# apa102-2020-stick.net
KiCad netlist of a schematic drawn in EAGLE
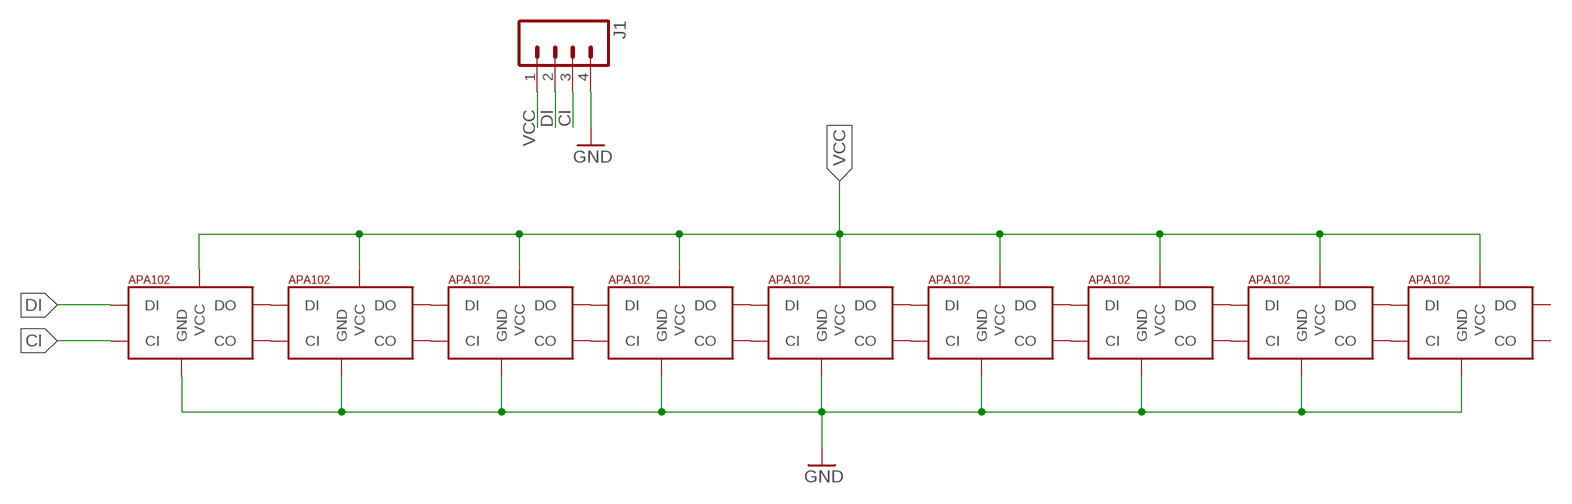
[diagram p0: schematic, sheet 1]

(export (version "E")
  (design (tool "Eeschema 10.0.6"))
  (components
    (comp (ref "J1")
      (value "M04LOCK")
      (footprint "eagle-import:1X04_LOCK")
      (libsource (lib "eagle-import") (part "M04LOCK"))
    )
    (comp (ref "U$1")
      (value "APA1022020")
      (footprint "eagle-import:APA102_2020")
      (libsource (lib "eagle-import") (part "APA1022020"))
    )
    (comp (ref "U$2")
      (value "APA1022020")
      (footprint "eagle-import:APA102_2020")
      (libsource (lib "eagle-import") (part "APA1022020"))
    )
    (comp (ref "U$3")
      (value "APA1022020")
      (footprint "eagle-import:APA102_2020")
      (libsource (lib "eagle-import") (part "APA1022020"))
    )
    (comp (ref "U$4")
      (value "APA1022020")
      (footprint "eagle-import:APA102_2020")
      (libsource (lib "eagle-import") (part "APA1022020"))
    )
    (comp (ref "U$5")
      (value "APA1022020")
      (footprint "eagle-import:APA102_2020")
      (libsource (lib "eagle-import") (part "APA1022020"))
    )
    (comp (ref "U$6")
      (value "APA1022020")
      (footprint "eagle-import:APA102_2020")
      (libsource (lib "eagle-import") (part "APA1022020"))
    )
    (comp (ref "U$7")
      (value "APA1022020")
      (footprint "eagle-import:APA102_2020")
      (libsource (lib "eagle-import") (part "APA1022020"))
    )
    (comp (ref "U$8")
      (value "APA1022020")
      (footprint "eagle-import:APA102_2020")
      (libsource (lib "eagle-import") (part "APA1022020"))
    )
    (comp (ref "U$9")
      (value "APA1022020")
      (footprint "eagle-import:APA102_2020")
      (libsource (lib "eagle-import") (part "APA1022020"))
    )
  )
  (nets
    (net (code "1") (name "CI") (class "Default")
      (node (ref "J1") (pin "3") (pinfunction "3_3") (pintype "passive"))
      (node (ref "U$1") (pin "C_IN") (pinfunction "CI_C_IN") (pintype "bidirectional"))
    )
    (net (code "2") (name "DI") (class "Default")
      (node (ref "J1") (pin "2") (pinfunction "2_2") (pintype "passive"))
      (node (ref "U$1") (pin "D_IN") (pinfunction "DI_D_IN") (pintype "bidirectional"))
    )
    (net (code "3") (name "GND") (class "Default")
      (node (ref "J1") (pin "4") (pinfunction "4_4") (pintype "passive"))
      (node (ref "U$1") (pin "GND") (pinfunction "GND_GND") (pintype "bidirectional"))
      (node (ref "U$2") (pin "GND") (pinfunction "GND_GND") (pintype "bidirectional"))
      (node (ref "U$3") (pin "GND") (pinfunction "GND_GND") (pintype "bidirectional"))
      (node (ref "U$4") (pin "GND") (pinfunction "GND_GND") (pintype "bidirectional"))
      (node (ref "U$5") (pin "GND") (pinfunction "GND_GND") (pintype "bidirectional"))
      (node (ref "U$6") (pin "GND") (pinfunction "GND_GND") (pintype "bidirectional"))
      (node (ref "U$7") (pin "GND") (pinfunction "GND_GND") (pintype "bidirectional"))
      (node (ref "U$8") (pin "GND") (pinfunction "GND_GND") (pintype "bidirectional"))
      (node (ref "U$9") (pin "GND") (pinfunction "GND_GND") (pintype "bidirectional"))
    )
    (net (code "4") (name "Net-(U$1-CO)") (class "Default")
      (node (ref "U$1") (pin "CL_OUT") (pinfunction "CO_CL_OUT") (pintype "bidirectional"))
      (node (ref "U$2") (pin "C_IN") (pinfunction "CI_C_IN") (pintype "bidirectional"))
    )
    (net (code "5") (name "Net-(U$1-DO)") (class "Default")
      (node (ref "U$1") (pin "D_OUT") (pinfunction "DO_D_OUT") (pintype "bidirectional"))
      (node (ref "U$2") (pin "D_IN") (pinfunction "DI_D_IN") (pintype "bidirectional"))
    )
    (net (code "6") (name "Net-(U$2-CO)") (class "Default")
      (node (ref "U$2") (pin "CL_OUT") (pinfunction "CO_CL_OUT") (pintype "bidirectional"))
      (node (ref "U$3") (pin "C_IN") (pinfunction "CI_C_IN") (pintype "bidirectional"))
    )
    (net (code "7") (name "Net-(U$2-DO)") (class "Default")
      (node (ref "U$2") (pin "D_OUT") (pinfunction "DO_D_OUT") (pintype "bidirectional"))
      (node (ref "U$3") (pin "D_IN") (pinfunction "DI_D_IN") (pintype "bidirectional"))
    )
    (net (code "8") (name "Net-(U$3-CO)") (class "Default")
      (node (ref "U$3") (pin "CL_OUT") (pinfunction "CO_CL_OUT") (pintype "bidirectional"))
      (node (ref "U$4") (pin "C_IN") (pinfunction "CI_C_IN") (pintype "bidirectional"))
    )
    (net (code "9") (name "Net-(U$3-DO)") (class "Default")
      (node (ref "U$3") (pin "D_OUT") (pinfunction "DO_D_OUT") (pintype "bidirectional"))
      (node (ref "U$4") (pin "D_IN") (pinfunction "DI_D_IN") (pintype "bidirectional"))
    )
    (net (code "10") (name "Net-(U$4-CO)") (class "Default")
      (node (ref "U$4") (pin "CL_OUT") (pinfunction "CO_CL_OUT") (pintype "bidirectional"))
      (node (ref "U$5") (pin "C_IN") (pinfunction "CI_C_IN") (pintype "bidirectional"))
    )
    (net (code "11") (name "Net-(U$4-DO)") (class "Default")
      (node (ref "U$4") (pin "D_OUT") (pinfunction "DO_D_OUT") (pintype "bidirectional"))
      (node (ref "U$5") (pin "D_IN") (pinfunction "DI_D_IN") (pintype "bidirectional"))
    )
    (net (code "12") (name "Net-(U$5-CO)") (class "Default")
      (node (ref "U$5") (pin "CL_OUT") (pinfunction "CO_CL_OUT") (pintype "bidirectional"))
      (node (ref "U$6") (pin "C_IN") (pinfunction "CI_C_IN") (pintype "bidirectional"))
    )
    (net (code "13") (name "Net-(U$5-DO)") (class "Default")
      (node (ref "U$5") (pin "D_OUT") (pinfunction "DO_D_OUT") (pintype "bidirectional"))
      (node (ref "U$6") (pin "D_IN") (pinfunction "DI_D_IN") (pintype "bidirectional"))
    )
    (net (code "14") (name "Net-(U$6-CO)") (class "Default")
      (node (ref "U$6") (pin "CL_OUT") (pinfunction "CO_CL_OUT") (pintype "bidirectional"))
      (node (ref "U$7") (pin "C_IN") (pinfunction "CI_C_IN") (pintype "bidirectional"))
    )
    (net (code "15") (name "Net-(U$6-DO)") (class "Default")
      (node (ref "U$6") (pin "D_OUT") (pinfunction "DO_D_OUT") (pintype "bidirectional"))
      (node (ref "U$7") (pin "D_IN") (pinfunction "DI_D_IN") (pintype "bidirectional"))
    )
    (net (code "16") (name "Net-(U$7-CO)") (class "Default")
      (node (ref "U$7") (pin "CL_OUT") (pinfunction "CO_CL_OUT") (pintype "bidirectional"))
      (node (ref "U$8") (pin "C_IN") (pinfunction "CI_C_IN") (pintype "bidirectional"))
    )
    (net (code "17") (name "Net-(U$7-DO)") (class "Default")
      (node (ref "U$7") (pin "D_OUT") (pinfunction "DO_D_OUT") (pintype "bidirectional"))
      (node (ref "U$8") (pin "D_IN") (pinfunction "DI_D_IN") (pintype "bidirectional"))
    )
    (net (code "18") (name "Net-(U$8-CO)") (class "Default")
      (node (ref "U$8") (pin "CL_OUT") (pinfunction "CO_CL_OUT") (pintype "bidirectional"))
      (node (ref "U$9") (pin "C_IN") (pinfunction "CI_C_IN") (pintype "bidirectional"))
    )
    (net (code "19") (name "Net-(U$8-DO)") (class "Default")
      (node (ref "U$8") (pin "D_OUT") (pinfunction "DO_D_OUT") (pintype "bidirectional"))
      (node (ref "U$9") (pin "D_IN") (pinfunction "DI_D_IN") (pintype "bidirectional"))
    )
    (net (code "20") (name "VCC") (class "Default")
      (node (ref "J1") (pin "1") (pinfunction "1_1") (pintype "passive"))
      (node (ref "U$1") (pin "V_CC") (pinfunction "VCC_V_CC") (pintype "bidirectional"))
      (node (ref "U$2") (pin "V_CC") (pinfunction "VCC_V_CC") (pintype "bidirectional"))
      (node (ref "U$3") (pin "V_CC") (pinfunction "VCC_V_CC") (pintype "bidirectional"))
      (node (ref "U$4") (pin "V_CC") (pinfunction "VCC_V_CC") (pintype "bidirectional"))
      (node (ref "U$5") (pin "V_CC") (pinfunction "VCC_V_CC") (pintype "bidirectional"))
      (node (ref "U$6") (pin "V_CC") (pinfunction "VCC_V_CC") (pintype "bidirectional"))
      (node (ref "U$7") (pin "V_CC") (pinfunction "VCC_V_CC") (pintype "bidirectional"))
      (node (ref "U$8") (pin "V_CC") (pinfunction "VCC_V_CC") (pintype "bidirectional"))
      (node (ref "U$9") (pin "V_CC") (pinfunction "VCC_V_CC") (pintype "bidirectional"))
    )
    (net (code "21") (name "unconnected-(U$9-CO-PadCL_OUT)") (class "Default")
      (node (ref "U$9") (pin "CL_OUT") (pinfunction "CO_CL_OUT") (pintype "bidirectional"))
    )
    (net (code "22") (name "unconnected-(U$9-DO-PadD_OUT)") (class "Default")
      (node (ref "U$9") (pin "D_OUT") (pinfunction "DO_D_OUT") (pintype "bidirectional"))
    )
  )
)
